# power2pix.net
KiCad netlist of a schematic drawn in Altium Designer
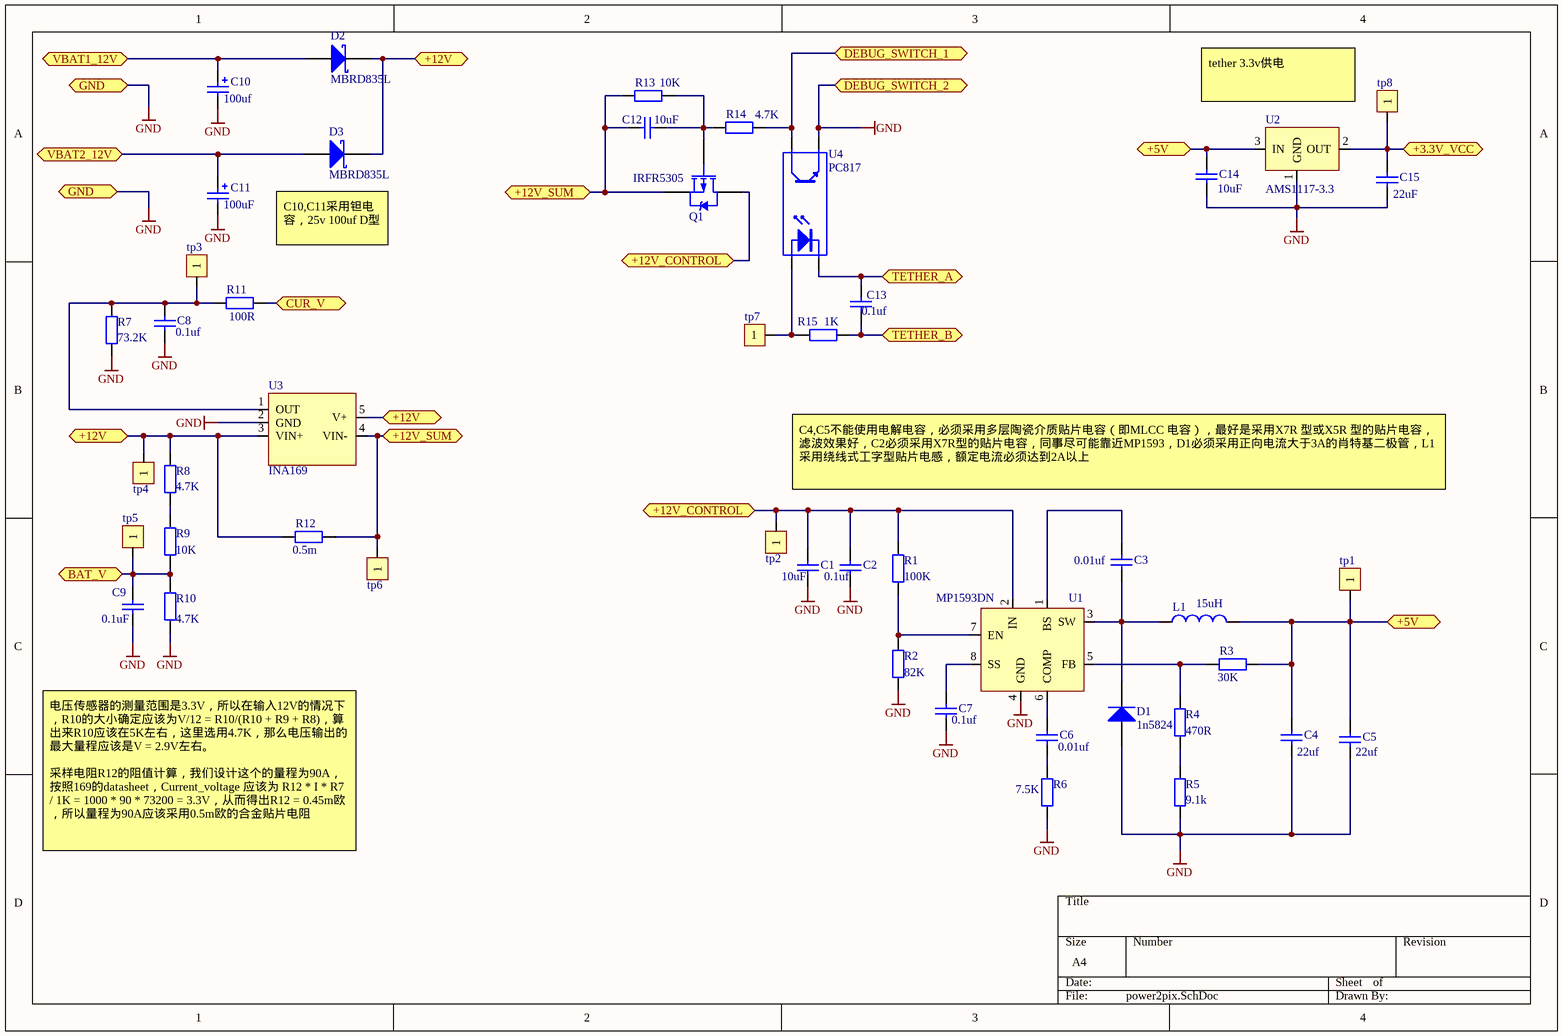
[diagram p0: power2pix.SchDoc]

(export (version "E")
  (design (tool "Eeschema 10.0.6"))
  (components
    (comp (ref "C1")
      (value "10uF")
      (footprint "C1206")
      (description "Capacitor")
      (fields (field (name "Comment") "Cap") (field (name "PUBLISHER") "Altium Limited"))
      (libsource (lib "Miscellaneous Devices") (part "Cap"))
    )
    (comp (ref "C2")
      (value "0.1uf")
      (footprint "6-0805_M")
      (description "Capacitor")
      (fields (field (name "Comment") "Cap") (field (name "PUBLISHER") "Altium Limited"))
      (libsource (lib "Miscellaneous Devices") (part "Cap"))
    )
    (comp (ref "C3")
      (value "0.01uf")
      (footprint "0603")
      (description "Capacitor")
      (fields (field (name "Comment") "Cap") (field (name "PUBLISHER") "Altium Limited"))
      (libsource (lib "Miscellaneous Devices") (part "Cap"))
    )
    (comp (ref "C4")
      (value "22uf")
      (footprint "C1206")
      (description "Capacitor")
      (fields (field (name "Comment") "Cap") (field (name "PUBLISHER") "Altium Limited"))
      (libsource (lib "Miscellaneous Devices") (part "Cap"))
    )
    (comp (ref "C5")
      (value "22uf")
      (footprint "C1206")
      (description "Capacitor")
      (fields (field (name "Comment") "Cap") (field (name "PUBLISHER") "Altium Limited"))
      (libsource (lib "Miscellaneous Devices") (part "Cap"))
    )
    (comp (ref "C6")
      (value "0.01uf")
      (footprint "0603")
      (description "Capacitor")
      (fields (field (name "Comment") "Cap") (field (name "PUBLISHER") "Altium Limited"))
      (libsource (lib "Miscellaneous Devices") (part "Cap"))
    )
    (comp (ref "C7")
      (value "0.1uf")
      (footprint "6-0805_M")
      (description "Capacitor")
      (fields (field (name "Comment") "Cap") (field (name "PUBLISHER") "Altium Limited"))
      (libsource (lib "Miscellaneous Devices") (part "Cap"))
    )
    (comp (ref "C8")
      (value "0.1uf")
      (footprint "6-0805_M")
      (description "Capacitor")
      (fields (field (name "Comment") "Cap") (field (name "PUBLISHER") "Altium Limited"))
      (libsource (lib "Miscellaneous Devices") (part "Cap"))
    )
    (comp (ref "C9")
      (value "0.1uF")
      (footprint "6-0805_M")
      (description "Capacitor")
      (fields (field (name "Comment") "Cap") (field (name "PUBLISHER") "Altium Limited"))
      (libsource (lib "Miscellaneous Devices") (part "Cap"))
    )
    (comp (ref "C10")
      (value "100uf")
      (footprint "7343")
      (description "Polarized Capacitor (Axial)")
      (fields (field (name "Comment") "Cap Pol2") (field (name "PUBLISHER") "Altium Limited"))
      (libsource (lib "Miscellaneous Devices") (part "Cap Pol2"))
    )
    (comp (ref "C11")
      (value "100uF")
      (footprint "7343")
      (description "Polarized Capacitor (Axial)")
      (fields (field (name "Comment") "Cap Pol2") (field (name "PUBLISHER") "Altium Limited"))
      (libsource (lib "Miscellaneous Devices") (part "Cap Pol2"))
    )
    (comp (ref "C12")
      (value "10uF")
      (footprint "C1206")
      (description "Capacitor")
      (fields (field (name "Comment") "Cap") (field (name "PUBLISHER") "Altium Limited"))
      (libsource (lib "Miscellaneous Devices") (part "Cap"))
    )
    (comp (ref "C13")
      (value "0.1uf")
      (footprint "6-0805_M")
      (description "Capacitor")
      (fields (field (name "Comment") "Cap") (field (name "PUBLISHER") "Altium Limited"))
      (libsource (lib "Miscellaneous Devices") (part "Cap"))
    )
    (comp (ref "C14")
      (value "10uF")
      (footprint "1206")
      (description "Capacitor")
      (fields (field (name "Comment") "Cap") (field (name "PUBLISHER") "Altium Limited"))
      (libsource (lib "Miscellaneous Devices") (part "Cap"))
    )
    (comp (ref "C15")
      (value "22uF")
      (footprint "my0603")
      (description "Capacitor")
      (fields (field (name "Comment") "Cap") (field (name "PUBLISHER") "Altium Limited"))
      (libsource (lib "Miscellaneous Devices") (part "Cap"))
    )
    (comp (ref "D1")
      (value "1n5824")
      (footprint "1N5824")
      (description "Default Diode")
      (fields (field (name "PUBLISHER") "Altium Limited"))
      (libsource (lib "Miscellaneous Devices") (part "Diode"))
    )
    (comp (ref "D2")
      (value "MBRD835L")
      (footprint "MBRD835L")
      (description "Schottky Rectifier")
      (fields (field (name "PUBLISHER") "Altium Limited"))
      (libsource (lib "Miscellaneous Devices") (part "Diode 11DQ03"))
    )
    (comp (ref "D3")
      (value "MBRD835L")
      (footprint "MBRD835L")
      (description "Schottky Rectifier")
      (fields (field (name "PUBLISHER") "Altium Limited"))
      (libsource (lib "Miscellaneous Devices") (part "Diode 11DQ03"))
    )
    (comp (ref "L1")
      (value "15uH")
      (footprint "0630")
      (description "Inductor")
      (fields (field (name "PUBLISHER") "Altium Limited"))
      (libsource (lib "Miscellaneous Devices") (part "Inductor"))
    )
    (comp (ref "Q1")
      (value "IRFR5305")
      (footprint "TO-252AA")
      (description "P-Channel Power MOSFET")
      (fields (field (name "PUBLISHER") "Altium Limited"))
      (libsource (lib "Miscellaneous Devices") (part "PMOS-2"))
    )
    (comp (ref "R1")
      (value "100K")
      (footprint "6-0805_M")
      (description "Resistor")
      (fields (field (name "Comment") "Res2") (field (name "PUBLISHER") "Altium Limited"))
      (libsource (lib "") (part "Res2_1"))
    )
    (comp (ref "R2")
      (value "82K")
      (footprint "6-0805_M")
      (description "Resistor")
      (fields (field (name "Comment") "Res2") (field (name "PUBLISHER") "Altium Limited"))
      (libsource (lib "") (part "Res2_1"))
    )
    (comp (ref "R3")
      (value "30K")
      (footprint "6-0805_M")
      (description "Resistor")
      (fields (field (name "Comment") "Res2") (field (name "PUBLISHER") "Altium Limited"))
      (libsource (lib "") (part "Res2_2"))
    )
    (comp (ref "R4")
      (value "470R")
      (footprint "6-0805_M")
      (description "Resistor")
      (fields (field (name "Comment") "Res2") (field (name "PUBLISHER") "Altium Limited"))
      (libsource (lib "") (part "Res2_1"))
    )
    (comp (ref "R5")
      (value "9.1k")
      (footprint "6-0805_M")
      (description "Resistor")
      (fields (field (name "Comment") "Res2") (field (name "PUBLISHER") "Altium Limited"))
      (libsource (lib "") (part "Res2_1"))
    )
    (comp (ref "R6")
      (value "7.5K")
      (footprint "6-0805_M")
      (description "Resistor")
      (fields (field (name "Comment") "Res2") (field (name "PUBLISHER") "Altium Limited"))
      (libsource (lib "") (part "Res2_1"))
    )
    (comp (ref "R7")
      (value "73.2K")
      (footprint "my0603")
      (description "Resistor")
      (fields (field (name "Comment") "Res2") (field (name "PUBLISHER") "Altium Limited"))
      (libsource (lib "") (part "Res2_1"))
    )
    (comp (ref "R8")
      (value "4.7K")
      (footprint "6-0805_M")
      (description "Resistor")
      (fields (field (name "Comment") "Res2") (field (name "PUBLISHER") "Altium Limited"))
      (libsource (lib "") (part "Res2_1"))
    )
    (comp (ref "R9")
      (value "10K")
      (footprint "6-0805_M")
      (description "Resistor")
      (fields (field (name "Comment") "Res2") (field (name "PUBLISHER") "Altium Limited"))
      (libsource (lib "") (part "Res2_1"))
    )
    (comp (ref "R10")
      (value "4.7K")
      (footprint "6-0805_M")
      (description "Resistor")
      (fields (field (name "Comment") "Res2") (field (name "PUBLISHER") "Altium Limited"))
      (libsource (lib "") (part "Res2_1"))
    )
    (comp (ref "R11")
      (value "100R")
      (footprint "6-0805_M")
      (description "Resistor")
      (fields (field (name "Comment") "Res2") (field (name "PUBLISHER") "Altium Limited"))
      (libsource (lib "Miscellaneous Devices") (part "Res2"))
    )
    (comp (ref "R12")
      (value "0.5m")
      (footprint "2512")
      (description "Resistor")
      (fields (field (name "Comment") "Res2") (field (name "PUBLISHER") "Altium Limited"))
      (libsource (lib "Miscellaneous Devices") (part "Res2"))
    )
    (comp (ref "R13")
      (value "10K")
      (footprint "6-0805_M")
      (description "Resistor")
      (fields (field (name "Comment") "Res2") (field (name "PUBLISHER") "Altium Limited"))
      (libsource (lib "Miscellaneous Devices") (part "Res2"))
    )
    (comp (ref "R14")
      (value "4.7K")
      (footprint "6-0805_M")
      (description "Resistor")
      (fields (field (name "Comment") "Res2") (field (name "PUBLISHER") "Altium Limited"))
      (libsource (lib "Miscellaneous Devices") (part "Res2"))
    )
    (comp (ref "R15")
      (value "1K")
      (footprint "6-0805_M")
      (description "Resistor")
      (fields (field (name "Comment") "Res2") (field (name "PUBLISHER") "Altium Limited"))
      (libsource (lib "Miscellaneous Devices") (part "Res2"))
    )
    (comp (ref "tp1") (value "tp") (footprint "testpoint") (libsource (lib "") (part "tp_1")))
    (comp (ref "tp2") (value "tp") (footprint "testpoint") (libsource (lib "power2pix_sch_lib") (part "tp")))
    (comp (ref "tp3") (value "tp") (footprint "testpoint") (libsource (lib "") (part "tp_1")))
    (comp (ref "tp4") (value "tp") (footprint "testpoint") (libsource (lib "power2pix_sch_lib") (part "tp")))
    (comp (ref "tp5") (value "tp") (footprint "testpoint") (libsource (lib "") (part "tp_1")))
    (comp (ref "tp6") (value "tp") (footprint "testpoint") (libsource (lib "power2pix_sch_lib") (part "tp")))
    (comp (ref "tp7") (value "tp") (footprint "testpoint") (libsource (lib "") (part "tp_2")))
    (comp (ref "tp8") (value "tp") (footprint "testpoint") (libsource (lib "") (part "tp_1")))
    (comp (ref "U1")
      (value "MP1593DN")
      (footprint "SO8_M")
      (libsource (lib "power2pix_sch_lib") (part "MP1593DN"))
    )
    (comp (ref "U2")
      (value "AMS1117-3.3")
      (footprint "SOT223_M")
      (libsource (lib "buoys_sch_lib") (part "AMS1117-3.3"))
    )
    (comp (ref "U3")
      (value "INA169")
      (footprint "SOT23-5")
      (libsource (lib "power2pix_sch_lib") (part "INA169"))
    )
    (comp (ref "U4")
      (value "PC817")
      (footprint "DIP-4")
      (description "4-Pin Phototransistor Optocoupler")
      (fields (field (name "PUBLISHER") "Altium Limited"))
      (libsource (lib "Miscellaneous Devices") (part "Optoisolator1"))
    )
  )
  (nets
    (net (code "1") (name "/+3.3V_VCC") (class "Default")
      (node (ref "C15") (pin "2") (pinfunction "2_2") (pintype "passive"))
      (node (ref "U2") (pin "2") (pinfunction "OUT_2") (pintype "passive"))
      (node (ref "tp8") (pin "1") (pinfunction "1_1") (pintype "passive"))
    )
    (net (code "2") (name "/+5V") (class "Default")
      (node (ref "C14") (pin "2") (pinfunction "2_2") (pintype "passive"))
      (node (ref "C4") (pin "2") (pinfunction "2_2") (pintype "passive"))
      (node (ref "C5") (pin "2") (pinfunction "2_2") (pintype "passive"))
      (node (ref "L1") (pin "2") (pinfunction "2_2") (pintype "passive"))
      (node (ref "R3") (pin "1") (pinfunction "1_1") (pintype "passive"))
      (node (ref "U2") (pin "3") (pinfunction "IN_3") (pintype "passive"))
      (node (ref "tp1") (pin "1") (pinfunction "1_1") (pintype "passive"))
    )
    (net (code "3") (name "/+12V") (class "Default")
      (node (ref "D2") (pin "2") (pinfunction "K_2") (pintype "passive"))
      (node (ref "D3") (pin "2") (pinfunction "K_2") (pintype "passive"))
      (node (ref "R12") (pin "1") (pinfunction "1_1") (pintype "passive"))
      (node (ref "R8") (pin "2") (pinfunction "2_2") (pintype "passive"))
      (node (ref "U3") (pin "3") (pinfunction "VIN+_3") (pintype "passive"))
      (node (ref "U3") (pin "5") (pinfunction "V+_5") (pintype "passive"))
      (node (ref "tp4") (pin "1") (pinfunction "1_1") (pintype "passive"))
    )
    (net (code "4") (name "/+12V_CONTROL") (class "Default")
      (node (ref "C1") (pin "2") (pinfunction "2_2") (pintype "passive"))
      (node (ref "C2") (pin "2") (pinfunction "2_2") (pintype "passive"))
      (node (ref "Q1") (pin "4") (pinfunction "D_4") (pintype "passive"))
      (node (ref "R1") (pin "2") (pinfunction "2_2") (pintype "passive"))
      (node (ref "U1") (pin "2") (pinfunction "IN_2") (pintype "passive"))
      (node (ref "tp2") (pin "1") (pinfunction "1_1") (pintype "passive"))
    )
    (net (code "5") (name "/+12V_SUM") (class "Default")
      (node (ref "C12") (pin "1") (pinfunction "1_1") (pintype "passive"))
      (node (ref "Q1") (pin "3") (pinfunction "S_3") (pintype "passive"))
      (node (ref "R12") (pin "2") (pinfunction "2_2") (pintype "passive"))
      (node (ref "R13") (pin "1") (pinfunction "1_1") (pintype "passive"))
      (node (ref "U3") (pin "4") (pinfunction "VIN-_4") (pintype "passive"))
      (node (ref "tp6") (pin "1") (pinfunction "1_1") (pintype "passive"))
    )
    (net (code "6") (name "/BAT_V") (class "Default")
      (node (ref "C9") (pin "2") (pinfunction "2_2") (pintype "passive"))
      (node (ref "R10") (pin "2") (pinfunction "2_2") (pintype "passive"))
      (node (ref "R9") (pin "1") (pinfunction "1_1") (pintype "passive"))
      (node (ref "tp5") (pin "1") (pinfunction "1_1") (pintype "passive"))
    )
    (net (code "7") (name "/CUR_V") (class "Default")
      (node (ref "R11") (pin "2") (pinfunction "2_2") (pintype "passive"))
    )
    (net (code "8") (name "/DEBUG_SWITCH_1") (class "Default")
      (node (ref "R14") (pin "2") (pinfunction "2_2") (pintype "passive"))
      (node (ref "U4") (pin "4") (pinfunction "C_4") (pintype "passive"))
    )
    (net (code "9") (name "/TETHER_A") (class "Default")
      (node (ref "C13") (pin "2") (pinfunction "2_2") (pintype "passive"))
      (node (ref "U4") (pin "2") (pinfunction "K_2") (pintype "passive"))
    )
    (net (code "10") (name "/TETHER_B") (class "Default")
      (node (ref "C13") (pin "1") (pinfunction "1_1") (pintype "passive"))
      (node (ref "R15") (pin "2") (pinfunction "2_2") (pintype "passive"))
    )
    (net (code "11") (name "/VBAT1_12V") (class "Default")
      (node (ref "C10") (pin "1") (pinfunction "1_1") (pintype "passive"))
      (node (ref "D2") (pin "1") (pinfunction "A_1") (pintype "passive"))
    )
    (net (code "12") (name "/VBAT2_12V") (class "Default")
      (node (ref "C11") (pin "1") (pinfunction "1_1") (pintype "passive"))
      (node (ref "D3") (pin "1") (pinfunction "A_1") (pintype "passive"))
    )
    (net (code "13") (name "GND") (class "Default")
      (node (ref "C1") (pin "1") (pinfunction "1_1") (pintype "passive"))
      (node (ref "C10") (pin "2") (pinfunction "2_2") (pintype "passive"))
      (node (ref "C11") (pin "2") (pinfunction "2_2") (pintype "passive"))
      (node (ref "C14") (pin "1") (pinfunction "1_1") (pintype "passive"))
      (node (ref "C15") (pin "1") (pinfunction "1_1") (pintype "passive"))
      (node (ref "C2") (pin "1") (pinfunction "1_1") (pintype "passive"))
      (node (ref "C4") (pin "1") (pinfunction "1_1") (pintype "passive"))
      (node (ref "C5") (pin "1") (pinfunction "1_1") (pintype "passive"))
      (node (ref "C7") (pin "1") (pinfunction "1_1") (pintype "passive"))
      (node (ref "C8") (pin "1") (pinfunction "1_1") (pintype "passive"))
      (node (ref "C9") (pin "1") (pinfunction "1_1") (pintype "passive"))
      (node (ref "D1") (pin "1") (pinfunction "A_1") (pintype "passive"))
      (node (ref "R10") (pin "1") (pinfunction "1_1") (pintype "passive"))
      (node (ref "R2") (pin "1") (pinfunction "1_1") (pintype "passive"))
      (node (ref "R5") (pin "1") (pinfunction "1_1") (pintype "passive"))
      (node (ref "R6") (pin "1") (pinfunction "1_1") (pintype "passive"))
      (node (ref "R7") (pin "1") (pinfunction "1_1") (pintype "passive"))
      (node (ref "U1") (pin "4") (pinfunction "GND_4") (pintype "passive"))
      (node (ref "U2") (pin "1") (pinfunction "GND_1") (pintype "passive"))
      (node (ref "U3") (pin "2") (pinfunction "GND_2") (pintype "passive"))
      (node (ref "U4") (pin "3") (pinfunction "E_3") (pintype "passive"))
    )
    (net (code "14") (name "Net-(C6-Pad1)") (class "Default")
      (node (ref "C6") (pin "1") (pinfunction "1_1") (pintype "passive"))
      (node (ref "R6") (pin "2") (pinfunction "2_2") (pintype "passive"))
    )
    (net (code "15") (name "Net-(D1-K)") (class "Default")
      (node (ref "C3") (pin "1") (pinfunction "1_1") (pintype "passive"))
      (node (ref "D1") (pin "2") (pinfunction "K_2") (pintype "passive"))
      (node (ref "L1") (pin "1") (pinfunction "1_1") (pintype "passive"))
      (node (ref "U1") (pin "3") (pinfunction "SW_3") (pintype "passive"))
    )
    (net (code "16") (name "Net-(Q1-G)") (class "Default")
      (node (ref "C12") (pin "2") (pinfunction "2_2") (pintype "passive"))
      (node (ref "Q1") (pin "1") (pinfunction "G_1") (pintype "passive"))
      (node (ref "R13") (pin "2") (pinfunction "2_2") (pintype "passive"))
      (node (ref "R14") (pin "1") (pinfunction "1_1") (pintype "passive"))
    )
    (net (code "17") (name "Net-(R4-Pad1)") (class "Default")
      (node (ref "R4") (pin "1") (pinfunction "1_1") (pintype "passive"))
      (node (ref "R5") (pin "2") (pinfunction "2_2") (pintype "passive"))
    )
    (net (code "18") (name "Net-(R8-Pad1)") (class "Default")
      (node (ref "R8") (pin "1") (pinfunction "1_1") (pintype "passive"))
      (node (ref "R9") (pin "2") (pinfunction "2_2") (pintype "passive"))
    )
    (net (code "19") (name "Net-(U1-BS)") (class "Default")
      (node (ref "C3") (pin "2") (pinfunction "2_2") (pintype "passive"))
      (node (ref "U1") (pin "1") (pinfunction "BS_1") (pintype "passive"))
    )
    (net (code "20") (name "Net-(U1-COMP)") (class "Default")
      (node (ref "C6") (pin "2") (pinfunction "2_2") (pintype "passive"))
      (node (ref "U1") (pin "6") (pinfunction "COMP_6") (pintype "passive"))
    )
    (net (code "21") (name "Net-(U1-EN)") (class "Default")
      (node (ref "R1") (pin "1") (pinfunction "1_1") (pintype "passive"))
      (node (ref "R2") (pin "2") (pinfunction "2_2") (pintype "passive"))
      (node (ref "U1") (pin "7") (pinfunction "EN_7") (pintype "passive"))
    )
    (net (code "22") (name "Net-(U1-FB)") (class "Default")
      (node (ref "R3") (pin "2") (pinfunction "2_2") (pintype "passive"))
      (node (ref "R4") (pin "2") (pinfunction "2_2") (pintype "passive"))
      (node (ref "U1") (pin "5") (pinfunction "FB_5") (pintype "passive"))
    )
    (net (code "23") (name "Net-(U1-SS)") (class "Default")
      (node (ref "C7") (pin "2") (pinfunction "2_2") (pintype "passive"))
      (node (ref "U1") (pin "8") (pinfunction "SS_8") (pintype "passive"))
    )
    (net (code "24") (name "Net-(U3-OUT)") (class "Default")
      (node (ref "C8") (pin "2") (pinfunction "2_2") (pintype "passive"))
      (node (ref "R11") (pin "1") (pinfunction "1_1") (pintype "passive"))
      (node (ref "R7") (pin "2") (pinfunction "2_2") (pintype "passive"))
      (node (ref "U3") (pin "1") (pinfunction "OUT_1") (pintype "passive"))
      (node (ref "tp3") (pin "1") (pinfunction "1_1") (pintype "passive"))
    )
    (net (code "25") (name "Net-(U4-A)") (class "Default")
      (node (ref "R15") (pin "1") (pinfunction "1_1") (pintype "passive"))
      (node (ref "U4") (pin "1") (pinfunction "A_1") (pintype "passive"))
      (node (ref "tp7") (pin "1") (pinfunction "1_1") (pintype "passive"))
    )
  )
)
